# EncoderWing.net
KiCad netlist of a schematic drawn in EAGLE
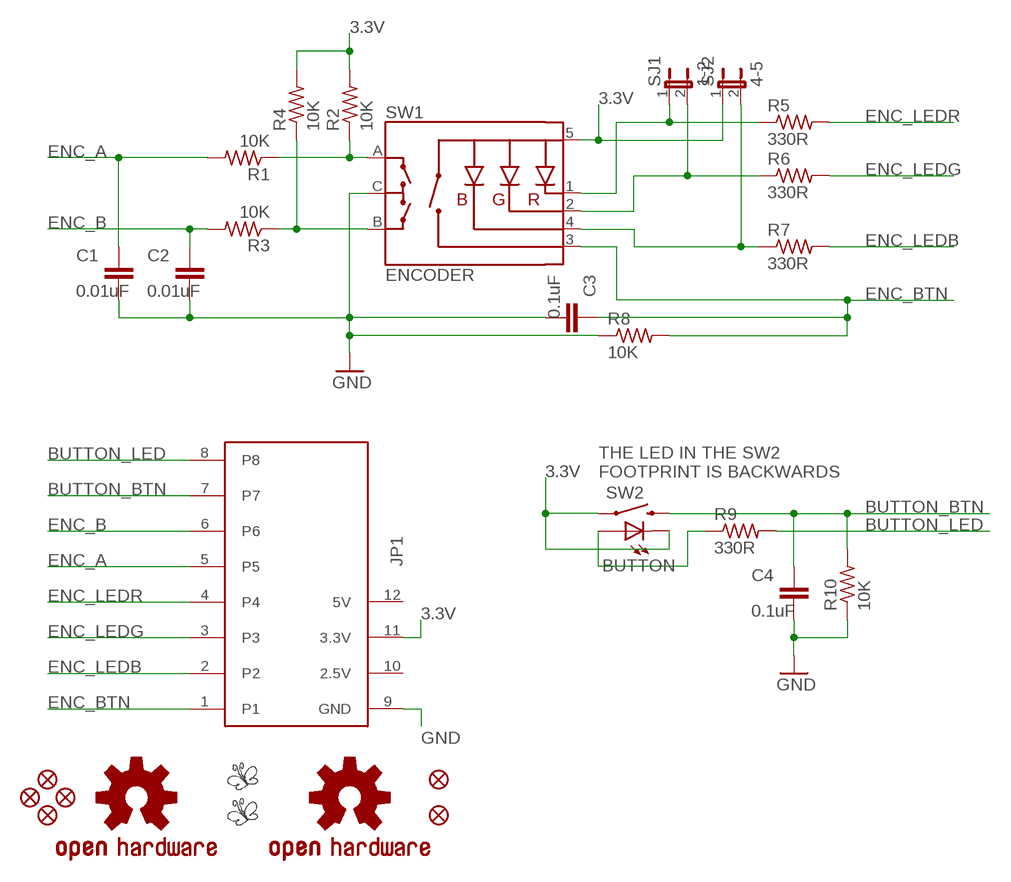
[diagram p0: schematic, sheet 1]

(export (version "E")
  (design (tool "Eeschema 10.0.6"))
  (components
    (comp (ref "C1")
      (value "0.01uF")
      (footprint "eagle-import:C0603")
      (libsource (lib "eagle-import") (part "C-EUC0603"))
    )
    (comp (ref "C2")
      (value "0.01uF")
      (footprint "eagle-import:C0603")
      (libsource (lib "eagle-import") (part "C-EUC0603"))
    )
    (comp (ref "C3")
      (value "0.1uF")
      (footprint "eagle-import:C0603")
      (libsource (lib "eagle-import") (part "C-EUC0603"))
    )
    (comp (ref "C4")
      (value "0.1uF")
      (footprint "eagle-import:C0603")
      (libsource (lib "eagle-import") (part "C-EUC0603"))
    )
    (comp (ref "FID1")
      (value "FIDUCIALUFIDUCIAL")
      (footprint "eagle-import:MICRO-FIDUCIAL")
      (libsource (lib "eagle-import") (part "FIDUCIALUFIDUCIAL"))
    )
    (comp (ref "FID2")
      (value "FIDUCIALUFIDUCIAL")
      (footprint "eagle-import:MICRO-FIDUCIAL")
      (libsource (lib "eagle-import") (part "FIDUCIALUFIDUCIAL"))
    )
    (comp (ref "FID3")
      (value "FIDUCIALUFIDUCIAL")
      (footprint "eagle-import:MICRO-FIDUCIAL")
      (libsource (lib "eagle-import") (part "FIDUCIALUFIDUCIAL"))
    )
    (comp (ref "FID4")
      (value "FIDUCIALUFIDUCIAL")
      (footprint "eagle-import:MICRO-FIDUCIAL")
      (libsource (lib "eagle-import") (part "FIDUCIALUFIDUCIAL"))
    )
    (comp (ref "FID5")
      (value "FIDUCIALUFIDUCIAL")
      (footprint "eagle-import:MICRO-FIDUCIAL")
      (libsource (lib "eagle-import") (part "FIDUCIALUFIDUCIAL"))
    )
    (comp (ref "FID6")
      (value "FIDUCIALUFIDUCIAL")
      (footprint "eagle-import:MICRO-FIDUCIAL")
      (libsource (lib "eagle-import") (part "FIDUCIALUFIDUCIAL"))
    )
    (comp (ref "JP1")
      (value "PAPILIO-WING-8BITS")
      (footprint "eagle-import:PAPILIO-WING-8BITS")
      (libsource (lib "eagle-import") (part "PAPILIO-WING-8BITS"))
    )
    (comp (ref "LOGO1")
      (value "BUTTERFLY_LOGO")
      (footprint "eagle-import:BUTTERFLY_LOGO")
      (libsource (lib "eagle-import") (part "BUTTERFLY_LOGO"))
    )
    (comp (ref "LOGO2")
      (value "BUTTERFLY_LOGO")
      (footprint "eagle-import:BUTTERFLY_LOGO")
      (libsource (lib "eagle-import") (part "BUTTERFLY_LOGO"))
    )
    (comp (ref "R1")
      (value "10K")
      (footprint "eagle-import:R0603")
      (libsource (lib "eagle-import") (part "R-US_R0603"))
    )
    (comp (ref "R2")
      (value "10K")
      (footprint "eagle-import:R0603")
      (libsource (lib "eagle-import") (part "R-US_R0603"))
    )
    (comp (ref "R3")
      (value "10K")
      (footprint "eagle-import:R0603")
      (libsource (lib "eagle-import") (part "R-US_R0603"))
    )
    (comp (ref "R4")
      (value "10K")
      (footprint "eagle-import:R0603")
      (libsource (lib "eagle-import") (part "R-US_R0603"))
    )
    (comp (ref "R5")
      (value "330R")
      (footprint "eagle-import:R0603")
      (libsource (lib "eagle-import") (part "R-US_R0603"))
    )
    (comp (ref "R6")
      (value "330R")
      (footprint "eagle-import:R0603")
      (libsource (lib "eagle-import") (part "R-US_R0603"))
    )
    (comp (ref "R7")
      (value "330R")
      (footprint "eagle-import:R0603")
      (libsource (lib "eagle-import") (part "R-US_R0603"))
    )
    (comp (ref "R8")
      (value "10K")
      (footprint "eagle-import:R0603")
      (libsource (lib "eagle-import") (part "R-US_R0603"))
    )
    (comp (ref "R9")
      (value "330R")
      (footprint "eagle-import:R0603")
      (libsource (lib "eagle-import") (part "R-US_R0603"))
    )
    (comp (ref "R10")
      (value "10K")
      (footprint "eagle-import:R0603")
      (libsource (lib "eagle-import") (part "R-US_R0603"))
    )
    (comp (ref "SJ1")
      (value "1-2")
      (footprint "eagle-import:SJ_2S-NO")
      (libsource (lib "eagle-import") (part "JUMPER-2SMD-NO"))
    )
    (comp (ref "SJ2")
      (value "4-5")
      (footprint "eagle-import:SJ_2S-NO")
      (libsource (lib "eagle-import") (part "JUMPER-2SMD-NO"))
    )
    (comp (ref "SW1")
      (value "ENCODER")
      (footprint "eagle-import:ENCODER_LED_3")
      (libsource (lib "eagle-import") (part "ENCODER_RGB_CA"))
    )
    (comp (ref "SW2")
      (value "BUTTON")
      (footprint "eagle-import:TACTILE-PTH-LED-12MM")
      (libsource (lib "eagle-import") (part "SWITCH-MOMENTARY-LEDPTH"))
    )
    (comp (ref "U$2")
      (value "OSHW-LOGOS")
      (footprint "eagle-import:OSHW-LOGO-S")
      (libsource (lib "eagle-import") (part "OSHW-LOGOS"))
    )
    (comp (ref "U$3")
      (value "OSHW-LOGOS")
      (footprint "eagle-import:OSHW-LOGO-S")
      (libsource (lib "eagle-import") (part "OSHW-LOGOS"))
    )
  )
  (nets
    (net (code "1") (name "/3.3V") (class "Default")
      (node (ref "JP1") (pin "11") (pinfunction "3.3V_11") (pintype "bidirectional"))
      (node (ref "R2") (pin "2") (pinfunction "2_2") (pintype "passive"))
      (node (ref "R4") (pin "2") (pinfunction "2_2") (pintype "passive"))
      (node (ref "SJ2") (pin "1") (pinfunction "1_1") (pintype "passive"))
      (node (ref "SW1") (pin "5") (pinfunction "+_5") (pintype "passive"))
      (node (ref "SW2") (pin "4") (pinfunction "1_4") (pintype "passive"))
      (node (ref "SW2") (pin "C") (pinfunction "C_C") (pintype "passive"))
    )
    (net (code "2") (name "/BUTTON_BTN") (class "Default")
      (node (ref "C4") (pin "1") (pinfunction "1_1") (pintype "passive"))
      (node (ref "JP1") (pin "7") (pinfunction "P7_7") (pintype "bidirectional"))
      (node (ref "R10") (pin "2") (pinfunction "2_2") (pintype "passive"))
      (node (ref "SW2") (pin "2") (pinfunction "2_2") (pintype "passive"))
    )
    (net (code "3") (name "/BUTTON_LED") (class "Default")
      (node (ref "JP1") (pin "8") (pinfunction "P8_8") (pintype "bidirectional"))
      (node (ref "R9") (pin "2") (pinfunction "2_2") (pintype "passive"))
    )
    (net (code "4") (name "/ENC_A") (class "Default")
      (node (ref "C1") (pin "1") (pinfunction "1_1") (pintype "passive"))
      (node (ref "JP1") (pin "5") (pinfunction "P5_5") (pintype "bidirectional"))
      (node (ref "R1") (pin "2") (pinfunction "2_2") (pintype "passive"))
    )
    (net (code "5") (name "/ENC_B") (class "Default")
      (node (ref "C2") (pin "1") (pinfunction "1_1") (pintype "passive"))
      (node (ref "JP1") (pin "6") (pinfunction "P6_6") (pintype "bidirectional"))
      (node (ref "R3") (pin "2") (pinfunction "2_2") (pintype "passive"))
    )
    (net (code "6") (name "/ENC_BTN") (class "Default")
      (node (ref "C3") (pin "1") (pinfunction "1_1") (pintype "passive"))
      (node (ref "JP1") (pin "1") (pinfunction "P1_1") (pintype "bidirectional"))
      (node (ref "R8") (pin "2") (pinfunction "2_2") (pintype "passive"))
      (node (ref "SW1") (pin "3") (pinfunction "SW_3") (pintype "passive"))
    )
    (net (code "7") (name "/ENC_LEDB") (class "Default")
      (node (ref "JP1") (pin "2") (pinfunction "P2_2") (pintype "bidirectional"))
      (node (ref "R7") (pin "2") (pinfunction "2_2") (pintype "passive"))
    )
    (net (code "8") (name "/ENC_LEDG") (class "Default")
      (node (ref "JP1") (pin "3") (pinfunction "P3_3") (pintype "bidirectional"))
      (node (ref "R6") (pin "2") (pinfunction "2_2") (pintype "passive"))
    )
    (net (code "9") (name "/ENC_LEDR") (class "Default")
      (node (ref "JP1") (pin "4") (pinfunction "P4_4") (pintype "bidirectional"))
      (node (ref "R5") (pin "2") (pinfunction "2_2") (pintype "passive"))
    )
    (net (code "10") (name "GND") (class "Default")
      (node (ref "C1") (pin "2") (pinfunction "2_2") (pintype "passive"))
      (node (ref "C2") (pin "2") (pinfunction "2_2") (pintype "passive"))
      (node (ref "C3") (pin "2") (pinfunction "2_2") (pintype "passive"))
      (node (ref "C4") (pin "2") (pinfunction "2_2") (pintype "passive"))
      (node (ref "JP1") (pin "9") (pinfunction "GND_9") (pintype "bidirectional"))
      (node (ref "R10") (pin "1") (pinfunction "1_1") (pintype "passive"))
      (node (ref "R8") (pin "1") (pinfunction "1_1") (pintype "passive"))
      (node (ref "SW1") (pin "C") (pinfunction "C_C") (pintype "bidirectional"))
    )
    (net (code "11") (name "Net-(R1-Pad1)") (class "Default")
      (node (ref "R1") (pin "1") (pinfunction "1_1") (pintype "passive"))
      (node (ref "R2") (pin "1") (pinfunction "1_1") (pintype "passive"))
      (node (ref "SW1") (pin "A") (pinfunction "A_A") (pintype "bidirectional"))
    )
    (net (code "12") (name "Net-(R3-Pad1)") (class "Default")
      (node (ref "R3") (pin "1") (pinfunction "1_1") (pintype "passive"))
      (node (ref "R4") (pin "1") (pinfunction "1_1") (pintype "passive"))
      (node (ref "SW1") (pin "B") (pinfunction "B_B") (pintype "bidirectional"))
    )
    (net (code "13") (name "Net-(R9-Pad1)") (class "Default")
      (node (ref "R9") (pin "1") (pinfunction "1_1") (pintype "passive"))
      (node (ref "SW2") (pin "A") (pinfunction "A_A") (pintype "passive"))
    )
    (net (code "14") (name "Net-(SW1--B)") (class "Default")
      (node (ref "R7") (pin "1") (pinfunction "1_1") (pintype "passive"))
      (node (ref "SJ2") (pin "2") (pinfunction "2_2") (pintype "passive"))
      (node (ref "SW1") (pin "4") (pinfunction "-B_4") (pintype "passive"))
    )
    (net (code "15") (name "Net-(SW1--G)") (class "Default")
      (node (ref "R6") (pin "1") (pinfunction "1_1") (pintype "passive"))
      (node (ref "SJ1") (pin "2") (pinfunction "2_2") (pintype "passive"))
      (node (ref "SW1") (pin "2") (pinfunction "-G_2") (pintype "passive"))
    )
    (net (code "16") (name "Net-(SW1--R)") (class "Default")
      (node (ref "R5") (pin "1") (pinfunction "1_1") (pintype "passive"))
      (node (ref "SJ1") (pin "1") (pinfunction "1_1") (pintype "passive"))
      (node (ref "SW1") (pin "1") (pinfunction "-R_1") (pintype "passive"))
    )
    (net (code "17") (name "unconnected-(JP1-2.5V-Pad10)") (class "Default")
      (node (ref "JP1") (pin "10") (pinfunction "2.5V_10") (pintype "bidirectional"))
    )
    (net (code "18") (name "unconnected-(JP1-5V-Pad12)") (class "Default")
      (node (ref "JP1") (pin "12") (pinfunction "5V_12") (pintype "bidirectional"))
    )
  )
)
